# Calentador_con_PID.net
KiCad netlist of a schematic drawn in EAGLE
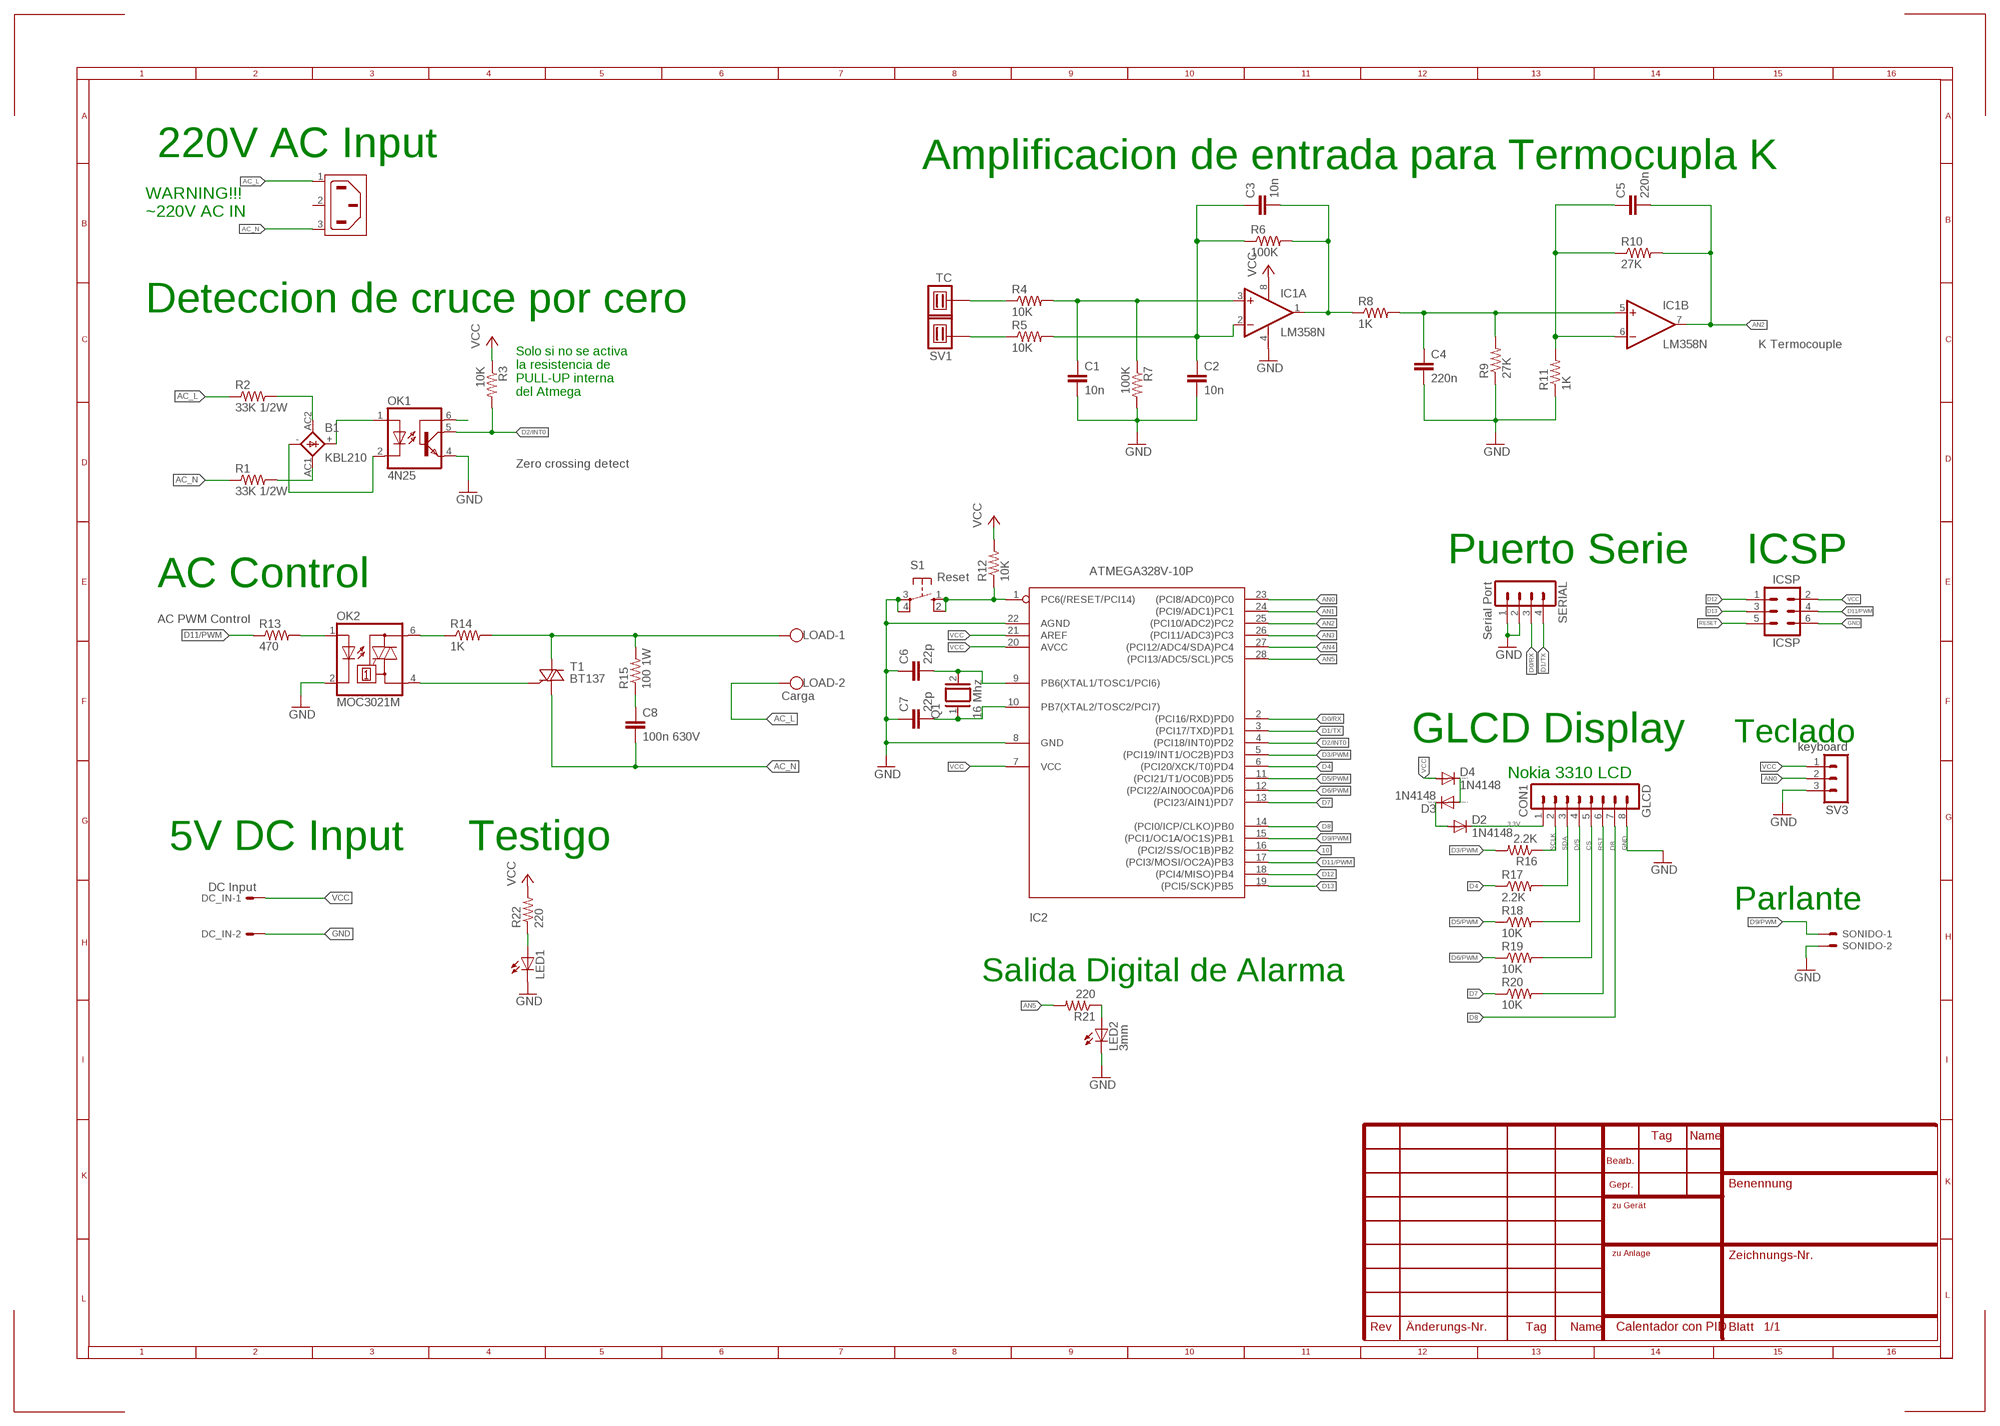
[diagram p0: schematic, sheet 1]

(export (version "E")
  (design (tool "Eeschema 10.0.6"))
  (components
    (comp (ref "B1")
      (value "KBL210")
      (footprint "eagle-import:KBL")
      (libsource (lib "eagle-import") (part "KBL"))
    )
    (comp (ref "C1")
      (value "10n")
      (footprint "eagle-import:C050-024X044")
      (libsource (lib "eagle-import") (part "C-EU050-024X044"))
    )
    (comp (ref "C2")
      (value "10n")
      (footprint "eagle-import:C050-024X044")
      (libsource (lib "eagle-import") (part "C-EU050-024X044"))
    )
    (comp (ref "C3")
      (value "10n")
      (footprint "eagle-import:C050-024X044")
      (libsource (lib "eagle-import") (part "C-EU050-024X044"))
    )
    (comp (ref "C4")
      (value "220n")
      (footprint "eagle-import:C050-025X075")
      (libsource (lib "eagle-import") (part "C-EU050-025X075"))
    )
    (comp (ref "C5")
      (value "220n")
      (footprint "eagle-import:C050-025X075")
      (libsource (lib "eagle-import") (part "C-EU050-025X075"))
    )
    (comp (ref "C6")
      (value "22p")
      (footprint "eagle-import:C050-025X075")
      (libsource (lib "eagle-import") (part "C-EU050-025X075"))
    )
    (comp (ref "C7")
      (value "22p")
      (footprint "eagle-import:C050-025X075")
      (libsource (lib "eagle-import") (part "C-EU050-025X075"))
    )
    (comp (ref "C8")
      (value "100n 630V")
      (footprint "eagle-import:C102-043X133")
      (libsource (lib "eagle-import") (part "C-EU102-043X133"))
    )
    (comp (ref "D2")
      (value "1N4148")
      (footprint "eagle-import:DO35-7")
      (libsource (lib "eagle-import") (part "1N4148DO35-7"))
    )
    (comp (ref "D3")
      (value "1N4148")
      (footprint "eagle-import:DO35-7")
      (libsource (lib "eagle-import") (part "1N4148DO35-7"))
    )
    (comp (ref "D4")
      (value "1N4148")
      (footprint "eagle-import:DO35-7")
      (libsource (lib "eagle-import") (part "1N4148DO35-7"))
    )
    (comp (ref "DC_IN")
      (value "DC Input")
      (footprint "eagle-import:22-23-2021")
      (fields (field (name "MF") "MOLEX") (field (name "MPN") "22-23-2021"))
      (libsource (lib "eagle-import") (part "22-23-2021"))
    )
    (comp (ref "GLCD")
      (value "CON1")
      (footprint "eagle-import:MA08-1")
      (libsource (lib "eagle-import") (part "MA08-1"))
    )
    (comp (ref "IC1")
      (value "LM358N")
      (footprint "eagle-import:DIL08")
      (libsource (lib "eagle-import") (part "LM358N"))
    )
    (comp (ref "IC2")
      (value "ATMEGA328V-10P")
      (footprint "eagle-import:DIL28-3")
      (libsource (lib "eagle-import") (part "ATMEGA328PV-10"))
    )
    (comp (ref "ICSP")
      (value "ICSP")
      (footprint "eagle-import:MA03-2")
      (libsource (lib "eagle-import") (part "MA03-2"))
    )
    (comp (ref "LED1")
      (value "LED3MM")
      (footprint "eagle-import:LED3MM")
      (libsource (lib "eagle-import") (part "LED3MM"))
    )
    (comp (ref "LED2")
      (value "3mm")
      (footprint "eagle-import:Q62902-B155")
      (libsource (lib "eagle-import") (part "LEDB155"))
    )
    (comp (ref "LOAD")
      (value "Carga")
      (footprint "eagle-import:W237-102")
      (fields (field (name "MPN") "237-102"))
      (libsource (lib "eagle-import") (part "W237-102"))
    )
    (comp (ref "OK1")
      (value "4N25")
      (footprint "eagle-import:DIL06")
      (fields (field (name "MF") "FAIRCHILD SEMICONDUCTOR") (field (name "MPN") "4N35"))
      (libsource (lib "eagle-import") (part "4N35"))
    )
    (comp (ref "OK2")
      (value "MOC3021M")
      (footprint "eagle-import:DIL06")
      (fields (field (name "MF") "FAIRCHILD SEMICONDUCTOR") (field (name "MPN") "MOC3021-M"))
      (libsource (lib "eagle-import") (part "MOC30M21"))
    )
    (comp (ref "Q1")
      (value "16 Mhz")
      (footprint "eagle-import:QS")
      (libsource (lib "eagle-import") (part "XTAL/S"))
    )
    (comp (ref "R1")
      (value "33K 1/2W")
      (footprint "eagle-import:0207_2V")
      (libsource (lib "eagle-import") (part "R-US_0207/2V"))
    )
    (comp (ref "R2")
      (value "33K 1/2W")
      (footprint "eagle-import:0207_2V")
      (libsource (lib "eagle-import") (part "R-US_0207/2V"))
    )
    (comp (ref "R3")
      (value "10K")
      (footprint "eagle-import:0207_7")
      (libsource (lib "eagle-import") (part "R-US_0207/7"))
    )
    (comp (ref "R4")
      (value "10K")
      (footprint "eagle-import:0207_7")
      (libsource (lib "eagle-import") (part "R-US_0207/7"))
    )
    (comp (ref "R5")
      (value "10K")
      (footprint "eagle-import:0207_7")
      (libsource (lib "eagle-import") (part "R-US_0207/7"))
    )
    (comp (ref "R6")
      (value "100K")
      (footprint "eagle-import:0207_2V")
      (libsource (lib "eagle-import") (part "R-US_0207/2V"))
    )
    (comp (ref "R7")
      (value "100K")
      (footprint "eagle-import:0207_7")
      (libsource (lib "eagle-import") (part "R-US_0207/7"))
    )
    (comp (ref "R8")
      (value "1K")
      (footprint "eagle-import:0207_2V")
      (libsource (lib "eagle-import") (part "R-US_0207/2V"))
    )
    (comp (ref "R9")
      (value "27K")
      (footprint "eagle-import:0207_7")
      (libsource (lib "eagle-import") (part "R-US_0207/7"))
    )
    (comp (ref "R10")
      (value "27K")
      (footprint "eagle-import:0207_2V")
      (libsource (lib "eagle-import") (part "R-US_0207/2V"))
    )
    (comp (ref "R11")
      (value "1K")
      (footprint "eagle-import:0207_7")
      (libsource (lib "eagle-import") (part "R-US_0207/7"))
    )
    (comp (ref "R12")
      (value "10K")
      (footprint "eagle-import:0207_15")
      (libsource (lib "eagle-import") (part "R-US_0207/15"))
    )
    (comp (ref "R13")
      (value "470")
      (footprint "eagle-import:0207_10")
      (libsource (lib "eagle-import") (part "R-US_0207/10"))
    )
    (comp (ref "R14")
      (value "1K")
      (footprint "eagle-import:0207_2V")
      (libsource (lib "eagle-import") (part "R-US_0207/2V"))
    )
    (comp (ref "R15")
      (value "100 1W")
      (footprint "eagle-import:0207_2V")
      (libsource (lib "eagle-import") (part "R-US_0207/2V"))
    )
    (comp (ref "R16")
      (value "2.2K")
      (footprint "eagle-import:0207_10")
      (libsource (lib "eagle-import") (part "R-US_0207/10"))
    )
    (comp (ref "R17")
      (value "2.2K")
      (footprint "eagle-import:0207_10")
      (libsource (lib "eagle-import") (part "R-US_0207/10"))
    )
    (comp (ref "R18")
      (value "10K")
      (footprint "eagle-import:0207_7")
      (libsource (lib "eagle-import") (part "R-US_0207/7"))
    )
    (comp (ref "R19")
      (value "10K")
      (footprint "eagle-import:0207_7")
      (libsource (lib "eagle-import") (part "R-US_0207/7"))
    )
    (comp (ref "R20")
      (value "10K")
      (footprint "eagle-import:0207_7")
      (libsource (lib "eagle-import") (part "R-US_0207/7"))
    )
    (comp (ref "R21")
      (value "220")
      (footprint "eagle-import:0207_7")
      (libsource (lib "eagle-import") (part "R-US_0207/7"))
    )
    (comp (ref "R22")
      (value "220")
      (footprint "eagle-import:0207_2V")
      (libsource (lib "eagle-import") (part "R-US_0207/2V"))
    )
    (comp (ref "S1")
      (value "Reset")
      (footprint "eagle-import:B3F-10XX")
      (fields (field (name "MPN") "B3F-1000"))
      (libsource (lib "eagle-import") (part "10-XX"))
    )
    (comp (ref "SERIAL")
      (value "Serial Port")
      (footprint "eagle-import:MA04-1")
      (libsource (lib "eagle-import") (part "MA04-1"))
    )
    (comp (ref "SONIDO")
      (value "22-23-2021")
      (footprint "eagle-import:22-23-2021")
      (fields (field (name "MF") "MOLEX"))
      (libsource (lib "eagle-import") (part "22-23-2021"))
    )
    (comp (ref "SV1")
      (value "TC")
      (footprint "eagle-import:THERMOCOUPLE")
      (libsource (lib "eagle-import") (part "THERMOCOUPLE"))
    )
    (comp (ref "SV3")
      (value "keyboard")
      (footprint "eagle-import:MA03-1")
      (libsource (lib "eagle-import") (part "MA03-1"))
    )
    (comp (ref "T1")
      (value "BT137")
      (footprint "eagle-import:TO220BV")
      (libsource (lib "eagle-import") (part "BT138-V"))
    )
    (comp (ref "X1")
      (value "6ESRM-P")
      (footprint "eagle-import:6ESRM-P")
      (fields (field (name "MF") "TYCO ELECTRONICS"))
      (libsource (lib "eagle-import") (part "6ESRM-P"))
    )
  )
  (nets
    (net (code "1") (name "/3.3V") (class "Default")
      (node (ref "D2") (pin "C") (pinfunction "C_C") (pintype "passive"))
      (node (ref "GLCD") (pin "1") (pinfunction "1_1") (pintype "passive"))
    )
    (net (code "2") (name "/CS") (class "Default")
      (node (ref "GLCD") (pin "5") (pinfunction "5_5") (pintype "passive"))
      (node (ref "R19") (pin "2") (pinfunction "2_2") (pintype "passive"))
    )
    (net (code "3") (name "/D{slash}S") (class "Default")
      (node (ref "GLCD") (pin "4") (pinfunction "4_4") (pintype "passive"))
      (node (ref "R18") (pin "2") (pinfunction "2_2") (pintype "passive"))
    )
    (net (code "4") (name "/RST") (class "Default")
      (node (ref "GLCD") (pin "6") (pinfunction "6_6") (pintype "passive"))
      (node (ref "R20") (pin "2") (pinfunction "2_2") (pintype "passive"))
    )
    (net (code "5") (name "/SCLK") (class "Default")
      (node (ref "GLCD") (pin "2") (pinfunction "2_2") (pintype "passive"))
      (node (ref "R16") (pin "1") (pinfunction "1_1") (pintype "passive"))
    )
    (net (code "6") (name "/SDA") (class "Default")
      (node (ref "GLCD") (pin "3") (pinfunction "3_3") (pintype "passive"))
      (node (ref "R17") (pin "2") (pinfunction "2_2") (pintype "passive"))
    )
    (net (code "7") (name "10") (class "Default")
      (node (ref "IC2") (pin "16") (pinfunction "(PCI2/SS/OC1B)PB2_16") (pintype "bidirectional"))
    )
    (net (code "8") (name "AC_L") (class "Default")
      (node (ref "LOAD") (pin "2") (pinfunction "KL_2") (pintype "passive"))
      (node (ref "R2") (pin "1") (pinfunction "1_1") (pintype "passive"))
      (node (ref "X1") (pin "1") (pinfunction "AC1_1") (pintype "passive"))
    )
    (net (code "9") (name "AC_N") (class "Default")
      (node (ref "C8") (pin "2") (pinfunction "2_2") (pintype "passive"))
      (node (ref "R1") (pin "1") (pinfunction "1_1") (pintype "passive"))
      (node (ref "T1") (pin "T1") (pinfunction "A1_T1") (pintype "passive"))
      (node (ref "X1") (pin "3") (pinfunction "AC2_3") (pintype "passive"))
    )
    (net (code "10") (name "AN0") (class "Default")
      (node (ref "IC2") (pin "23") (pinfunction "(PCI8/ADC0)PC0_23") (pintype "bidirectional"))
      (node (ref "SV3") (pin "2") (pinfunction "2_2") (pintype "passive"))
    )
    (net (code "11") (name "AN1") (class "Default")
      (node (ref "IC2") (pin "24") (pinfunction "(PCI9/ADC1)PC1_24") (pintype "bidirectional"))
    )
    (net (code "12") (name "AN2") (class "Default")
      (node (ref "C5") (pin "2") (pinfunction "2_2") (pintype "passive"))
      (node (ref "IC1") (pin "7") (pinfunction "OUT_7") (pintype "output"))
      (node (ref "IC2") (pin "25") (pinfunction "(PCI10/ADC2)PC2_25") (pintype "bidirectional"))
      (node (ref "R10") (pin "2") (pinfunction "2_2") (pintype "passive"))
    )
    (net (code "13") (name "AN3") (class "Default")
      (node (ref "IC2") (pin "26") (pinfunction "(PCI11/ADC3)PC3_26") (pintype "bidirectional"))
    )
    (net (code "14") (name "AN4") (class "Default")
      (node (ref "IC2") (pin "27") (pinfunction "(PCI12/ADC4/SDA)PC4_27") (pintype "bidirectional"))
    )
    (net (code "15") (name "AN5") (class "Default")
      (node (ref "IC2") (pin "28") (pinfunction "(PCI13/ADC5/SCL)PC5_28") (pintype "bidirectional"))
      (node (ref "R21") (pin "2") (pinfunction "2_2") (pintype "passive"))
    )
    (net (code "16") (name "D0{slash}RX") (class "Default")
      (node (ref "IC2") (pin "2") (pinfunction "(PCI16/RXD)PD0_2") (pintype "bidirectional"))
      (node (ref "SERIAL") (pin "3") (pinfunction "3_3") (pintype "passive"))
    )
    (net (code "17") (name "D1{slash}TX") (class "Default")
      (node (ref "IC2") (pin "3") (pinfunction "(PCI17/TXD)PD1_3") (pintype "bidirectional"))
      (node (ref "SERIAL") (pin "4") (pinfunction "4_4") (pintype "passive"))
    )
    (net (code "18") (name "D2{slash}INT0") (class "Default")
      (node (ref "IC2") (pin "4") (pinfunction "(PCI18/INT0)PD2_4") (pintype "bidirectional"))
      (node (ref "OK1") (pin "5") (pinfunction "COL_5") (pintype "passive"))
      (node (ref "R3") (pin "2") (pinfunction "2_2") (pintype "passive"))
    )
    (net (code "19") (name "D3{slash}PWM") (class "Default")
      (node (ref "IC2") (pin "5") (pinfunction "(PCI19/INT1/OC2B)PD3_5") (pintype "bidirectional"))
      (node (ref "R16") (pin "2") (pinfunction "2_2") (pintype "passive"))
    )
    (net (code "20") (name "D4") (class "Default")
      (node (ref "IC2") (pin "6") (pinfunction "(PCI20/XCK/T0)PD4_6") (pintype "bidirectional"))
      (node (ref "R17") (pin "1") (pinfunction "1_1") (pintype "passive"))
    )
    (net (code "21") (name "D5{slash}PWM") (class "Default")
      (node (ref "IC2") (pin "11") (pinfunction "(PCI21/T1/OC0B)PD5_11") (pintype "bidirectional"))
      (node (ref "R18") (pin "1") (pinfunction "1_1") (pintype "passive"))
    )
    (net (code "22") (name "D6{slash}PWM") (class "Default")
      (node (ref "IC2") (pin "12") (pinfunction "(PCI22/AIN0OC0A)PD6_12") (pintype "bidirectional"))
      (node (ref "R19") (pin "1") (pinfunction "1_1") (pintype "passive"))
    )
    (net (code "23") (name "D7") (class "Default")
      (node (ref "IC2") (pin "13") (pinfunction "(PCI23/AIN1)PD7_13") (pintype "bidirectional"))
      (node (ref "R20") (pin "1") (pinfunction "1_1") (pintype "passive"))
    )
    (net (code "24") (name "D8") (class "Default")
      (node (ref "GLCD") (pin "7") (pinfunction "7_7") (pintype "passive"))
      (node (ref "IC2") (pin "14") (pinfunction "(PCI0/ICP/CLKO)PB0_14") (pintype "bidirectional"))
    )
    (net (code "25") (name "D9{slash}PWM") (class "Default")
      (node (ref "IC2") (pin "15") (pinfunction "(PCI1/OC1A/OC1S)PB1_15") (pintype "bidirectional"))
      (node (ref "SONIDO") (pin "1") (pinfunction "S_1") (pintype "passive"))
    )
    (net (code "26") (name "D11{slash}PWM") (class "Default")
      (node (ref "IC2") (pin "17") (pinfunction "(PCI3/MOSI/OC2A)PB3_17") (pintype "bidirectional"))
      (node (ref "ICSP") (pin "4") (pinfunction "4_4") (pintype "passive"))
      (node (ref "R13") (pin "1") (pinfunction "1_1") (pintype "passive"))
    )
    (net (code "27") (name "D12") (class "Default")
      (node (ref "IC2") (pin "18") (pinfunction "(PCI4/MISO)PB4_18") (pintype "bidirectional"))
      (node (ref "ICSP") (pin "1") (pinfunction "1_1") (pintype "passive"))
    )
    (net (code "28") (name "D13") (class "Default")
      (node (ref "IC2") (pin "19") (pinfunction "(PCI5/SCK)PB5_19") (pintype "bidirectional"))
      (node (ref "ICSP") (pin "3") (pinfunction "3_3") (pintype "passive"))
    )
    (net (code "29") (name "GND") (class "Default")
      (node (ref "C1") (pin "2") (pinfunction "2_2") (pintype "passive"))
      (node (ref "C2") (pin "2") (pinfunction "2_2") (pintype "passive"))
      (node (ref "C4") (pin "2") (pinfunction "2_2") (pintype "passive"))
      (node (ref "C6") (pin "1") (pinfunction "1_1") (pintype "passive"))
      (node (ref "C7") (pin "1") (pinfunction "1_1") (pintype "passive"))
      (node (ref "DC_IN") (pin "2") (pinfunction "S_2") (pintype "passive"))
      (node (ref "GLCD") (pin "8") (pinfunction "8_8") (pintype "passive"))
      (node (ref "IC1") (pin "4") (pinfunction "V-_4") (pintype "power_in"))
      (node (ref "IC2") (pin "22") (pinfunction "AGND_22") (pintype "bidirectional"))
      (node (ref "IC2") (pin "8") (pinfunction "GND_8") (pintype "bidirectional"))
      (node (ref "ICSP") (pin "6") (pinfunction "6_6") (pintype "passive"))
      (node (ref "LED1") (pin "K") (pinfunction "C_K") (pintype "passive"))
      (node (ref "LED2") (pin "K") (pinfunction "C_K") (pintype "passive"))
      (node (ref "OK1") (pin "4") (pinfunction "EMI_4") (pintype "passive"))
      (node (ref "OK2") (pin "2") (pinfunction "C_2") (pintype "passive"))
      (node (ref "R11") (pin "1") (pinfunction "1_1") (pintype "passive"))
      (node (ref "R7") (pin "2") (pinfunction "2_2") (pintype "passive"))
      (node (ref "R9") (pin "1") (pinfunction "1_1") (pintype "passive"))
      (node (ref "S1") (pin "3") (pinfunction "P_3") (pintype "passive"))
      (node (ref "S1") (pin "4") (pinfunction "P1_4") (pintype "passive"))
      (node (ref "SERIAL") (pin "1") (pinfunction "1_1") (pintype "passive"))
      (node (ref "SERIAL") (pin "2") (pinfunction "2_2") (pintype "passive"))
      (node (ref "SONIDO") (pin "2") (pinfunction "S_2") (pintype "passive"))
      (node (ref "SV3") (pin "3") (pinfunction "3_3") (pintype "passive"))
    )
    (net (code "30") (name "Net-(B1-AC1)") (class "Default")
      (node (ref "B1") (pin "AC2") (pinfunction "AC1_AC2") (pintype "passive"))
      (node (ref "R2") (pin "2") (pinfunction "2_2") (pintype "passive"))
    )
    (net (code "31") (name "Net-(B1-AC2)") (class "Default")
      (node (ref "B1") (pin "AC1") (pinfunction "AC2_AC1") (pintype "passive"))
      (node (ref "R1") (pin "2") (pinfunction "2_2") (pintype "passive"))
    )
    (net (code "32") (name "Net-(C8-Pad1)") (class "Default")
      (node (ref "C8") (pin "1") (pinfunction "1_1") (pintype "passive"))
      (node (ref "R15") (pin "1") (pinfunction "1_1") (pintype "passive"))
    )
    (net (code "33") (name "Net-(D2-PadA)") (class "Default")
      (node (ref "D2") (pin "A") (pinfunction "A_A") (pintype "passive"))
      (node (ref "D3") (pin "C") (pinfunction "C_C") (pintype "passive"))
    )
    (net (code "34") (name "Net-(D3-PadA)") (class "Default")
      (node (ref "D3") (pin "A") (pinfunction "A_A") (pintype "passive"))
      (node (ref "D4") (pin "C") (pinfunction "C_C") (pintype "passive"))
    )
    (net (code "35") (name "Net-(IC1A-+IN)") (class "Default")
      (node (ref "C1") (pin "1") (pinfunction "1_1") (pintype "passive"))
      (node (ref "IC1") (pin "3") (pinfunction "+IN_3") (pintype "input"))
      (node (ref "R4") (pin "2") (pinfunction "2_2") (pintype "passive"))
      (node (ref "R7") (pin "1") (pinfunction "1_1") (pintype "passive"))
    )
    (net (code "36") (name "Net-(IC1A--IN)") (class "Default")
      (node (ref "C2") (pin "1") (pinfunction "1_1") (pintype "passive"))
      (node (ref "C3") (pin "1") (pinfunction "1_1") (pintype "passive"))
      (node (ref "IC1") (pin "2") (pinfunction "-IN_2") (pintype "input"))
      (node (ref "R5") (pin "2") (pinfunction "2_2") (pintype "passive"))
      (node (ref "R6") (pin "1") (pinfunction "1_1") (pintype "passive"))
    )
    (net (code "37") (name "Net-(IC1A-OUT)") (class "Default")
      (node (ref "C3") (pin "2") (pinfunction "2_2") (pintype "passive"))
      (node (ref "IC1") (pin "1") (pinfunction "OUT_1") (pintype "output"))
      (node (ref "R6") (pin "2") (pinfunction "2_2") (pintype "passive"))
      (node (ref "R8") (pin "1") (pinfunction "1_1") (pintype "passive"))
    )
    (net (code "38") (name "Net-(IC1B-+IN)") (class "Default")
      (node (ref "C4") (pin "1") (pinfunction "1_1") (pintype "passive"))
      (node (ref "IC1") (pin "5") (pinfunction "+IN_5") (pintype "input"))
      (node (ref "R8") (pin "2") (pinfunction "2_2") (pintype "passive"))
      (node (ref "R9") (pin "2") (pinfunction "2_2") (pintype "passive"))
    )
    (net (code "39") (name "Net-(IC1B--IN)") (class "Default")
      (node (ref "C5") (pin "1") (pinfunction "1_1") (pintype "passive"))
      (node (ref "IC1") (pin "6") (pinfunction "-IN_6") (pintype "input"))
      (node (ref "R10") (pin "1") (pinfunction "1_1") (pintype "passive"))
      (node (ref "R11") (pin "2") (pinfunction "2_2") (pintype "passive"))
    )
    (net (code "40") (name "Net-(IC2-PB6(XTAL1{slash}TOSC1{slash}PCI6))") (class "Default")
      (node (ref "C6") (pin "2") (pinfunction "2_2") (pintype "passive"))
      (node (ref "IC2") (pin "9") (pinfunction "PB6(XTAL1/TOSC1/PCI6)_9") (pintype "bidirectional"))
      (node (ref "Q1") (pin "2") (pinfunction "2_2") (pintype "passive"))
    )
    (net (code "41") (name "Net-(IC2-PB7(XTAL2{slash}TOSC2{slash}PCI7))") (class "Default")
      (node (ref "C7") (pin "2") (pinfunction "2_2") (pintype "passive"))
      (node (ref "IC2") (pin "10") (pinfunction "PB7(XTAL2/TOSC2/PCI7)_10") (pintype "bidirectional"))
      (node (ref "Q1") (pin "1") (pinfunction "1_1") (pintype "passive"))
    )
    (net (code "42") (name "Net-(LED1-PadA)") (class "Default")
      (node (ref "LED1") (pin "A") (pinfunction "A_A") (pintype "passive"))
      (node (ref "R22") (pin "1") (pinfunction "1_1") (pintype "passive"))
    )
    (net (code "43") (name "Net-(LED2-PadA)") (class "Default")
      (node (ref "LED2") (pin "A") (pinfunction "A_A") (pintype "passive"))
      (node (ref "R21") (pin "1") (pinfunction "1_1") (pintype "passive"))
    )
    (net (code "44") (name "Net-(LOADA-KL)") (class "Default")
      (node (ref "LOAD") (pin "1") (pinfunction "KL_1") (pintype "passive"))
      (node (ref "R14") (pin "2") (pinfunction "2_2") (pintype "passive"))
      (node (ref "R15") (pin "2") (pinfunction "2_2") (pintype "passive"))
      (node (ref "T1") (pin "T2") (pinfunction "A2_T2") (pintype "passive"))
    )
    (net (code "45") (name "Net-(OK1-A)") (class "Default")
      (node (ref "B1") (pin "+") (pinfunction "+_+") (pintype "passive"))
      (node (ref "OK1") (pin "1") (pinfunction "A_1") (pintype "passive"))
    )
    (net (code "46") (name "Net-(OK1-C)") (class "Default")
      (node (ref "B1") (pin "-") (pinfunction "-_-") (pintype "passive"))
      (node (ref "OK1") (pin "2") (pinfunction "C_2") (pintype "passive"))
    )
    (net (code "47") (name "Net-(OK2-A)") (class "Default")
      (node (ref "OK2") (pin "1") (pinfunction "A_1") (pintype "passive"))
      (node (ref "R13") (pin "2") (pinfunction "2_2") (pintype "passive"))
    )
    (net (code "48") (name "Net-(OK2-A1)") (class "Default")
      (node (ref "OK2") (pin "4") (pinfunction "A1_4") (pintype "passive"))
      (node (ref "T1") (pin "G") (pinfunction "G_G") (pintype "passive"))
    )
    (net (code "49") (name "Net-(OK2-A2)") (class "Default")
      (node (ref "OK2") (pin "6") (pinfunction "A2_6") (pintype "passive"))
      (node (ref "R14") (pin "1") (pinfunction "1_1") (pintype "passive"))
    )
    (net (code "50") (name "Net-(SV1-P$1)") (class "Default")
      (node (ref "R5") (pin "1") (pinfunction "1_1") (pintype "passive"))
      (node (ref "SV1") (pin "1") (pinfunction "P$1_1") (pintype "bidirectional"))
    )
    (net (code "51") (name "Net-(SV1-P$2)") (class "Default")
      (node (ref "R4") (pin "1") (pinfunction "1_1") (pintype "passive"))
      (node (ref "SV1") (pin "2") (pinfunction "P$2_2") (pintype "bidirectional"))
    )
    (net (code "52") (name "RESET") (class "Default")
      (node (ref "IC2") (pin "1") (pinfunction "PC6(/RESET/PCI14)_1") (pintype "bidirectional"))
      (node (ref "ICSP") (pin "5") (pinfunction "5_5") (pintype "passive"))
      (node (ref "R12") (pin "1") (pinfunction "1_1") (pintype "passive"))
      (node (ref "S1") (pin "1") (pinfunction "S_1") (pintype "passive"))
      (node (ref "S1") (pin "2") (pinfunction "S1_2") (pintype "passive"))
    )
    (net (code "53") (name "VCC") (class "Default")
      (node (ref "D4") (pin "A") (pinfunction "A_A") (pintype "passive"))
      (node (ref "DC_IN") (pin "1") (pinfunction "S_1") (pintype "passive"))
      (node (ref "IC1") (pin "8") (pinfunction "V+_8") (pintype "power_in"))
      (node (ref "IC2") (pin "20") (pinfunction "AVCC_20") (pintype "bidirectional"))
      (node (ref "IC2") (pin "21") (pinfunction "AREF_21") (pintype "bidirectional"))
      (node (ref "IC2") (pin "7") (pinfunction "VCC_7") (pintype "bidirectional"))
      (node (ref "ICSP") (pin "2") (pinfunction "2_2") (pintype "passive"))
      (node (ref "R12") (pin "2") (pinfunction "2_2") (pintype "passive"))
      (node (ref "R22") (pin "2") (pinfunction "2_2") (pintype "passive"))
      (node (ref "R3") (pin "1") (pinfunction "1_1") (pintype "passive"))
      (node (ref "SV3") (pin "1") (pinfunction "1_1") (pintype "passive"))
    )
    (net (code "54") (name "unconnected-(OK1-BAS-Pad6)") (class "Default")
      (node (ref "OK1") (pin "6") (pinfunction "BAS_6") (pintype "passive"))
    )
    (net (code "55") (name "unconnected-(X1-SH-Pad2)") (class "Default")
      (node (ref "X1") (pin "2") (pinfunction "SH_2") (pintype "passive"))
    )
  )
)
